# btob.net
KiCad netlist of a schematic drawn in EAGLE
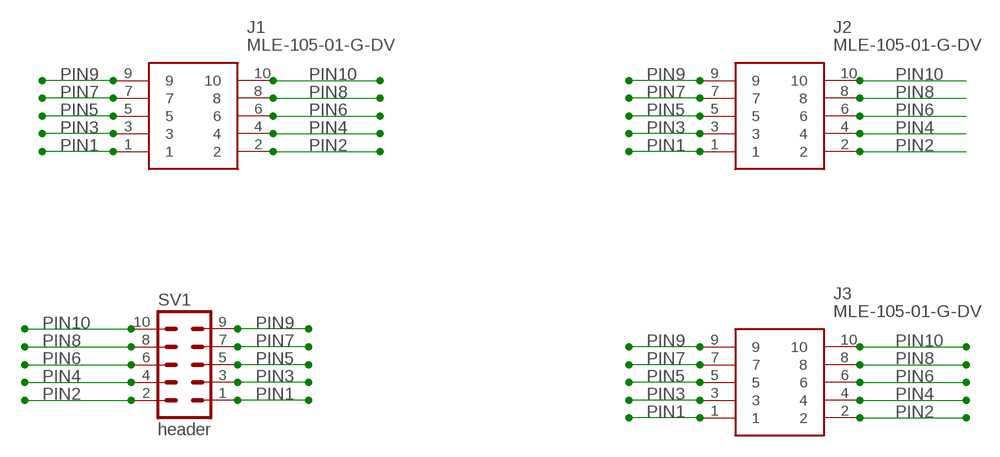
[diagram p0: schematic, sheet 1]

(export (version "E")
  (design (tool "Eeschema 10.0.6"))
  (components
    (comp (ref "J1")
      (value "MLE-105-01-G-DV")
      (footprint "eagle-import:MLE-105-01-G-DV")
      (fields (field (name "MOUSER_PART_NUMBER") "200-MLE10501GDV"))
      (libsource (lib "eagle-import") (part "MLE-105-01-G-DV"))
    )
    (comp (ref "J2")
      (value "MLE-105-01-G-DV")
      (footprint "eagle-import:MLE-105-01-G-DV")
      (fields (field (name "MOUSER_PART_NUMBER") "200-MLE10501GDV"))
      (libsource (lib "eagle-import") (part "MLE-105-01-G-DV"))
    )
    (comp (ref "J3")
      (value "MLE-105-01-G-DV")
      (footprint "eagle-import:MLE-105-01-G-DV")
      (fields (field (name "MOUSER_PART_NUMBER") "200-MLE10501GDV"))
      (libsource (lib "eagle-import") (part "MLE-105-01-G-DV"))
    )
    (comp (ref "SV1")
      (value "header")
      (footprint "eagle-import:MA05-2")
      (libsource (lib "eagle-import") (part "MA05-2"))
    )
  )
  (nets
    (net (code "1") (name "/PIN1") (class "Default")
      (node (ref "J1") (pin "1") (pinfunction "1_1") (pintype "bidirectional"))
      (node (ref "J2") (pin "1") (pinfunction "1_1") (pintype "bidirectional"))
      (node (ref "J3") (pin "1") (pinfunction "1_1") (pintype "bidirectional"))
      (node (ref "SV1") (pin "1") (pinfunction "1_1") (pintype "passive"))
    )
    (net (code "2") (name "/PIN2") (class "Default")
      (node (ref "J1") (pin "2") (pinfunction "2_2") (pintype "bidirectional"))
      (node (ref "J2") (pin "2") (pinfunction "2_2") (pintype "bidirectional"))
      (node (ref "J3") (pin "2") (pinfunction "2_2") (pintype "bidirectional"))
      (node (ref "SV1") (pin "2") (pinfunction "2_2") (pintype "passive"))
    )
    (net (code "3") (name "/PIN3") (class "Default")
      (node (ref "J1") (pin "3") (pinfunction "3_3") (pintype "bidirectional"))
      (node (ref "J2") (pin "3") (pinfunction "3_3") (pintype "bidirectional"))
      (node (ref "J3") (pin "3") (pinfunction "3_3") (pintype "bidirectional"))
      (node (ref "SV1") (pin "3") (pinfunction "3_3") (pintype "passive"))
    )
    (net (code "4") (name "/PIN4") (class "Default")
      (node (ref "J1") (pin "4") (pinfunction "4_4") (pintype "bidirectional"))
      (node (ref "J2") (pin "4") (pinfunction "4_4") (pintype "bidirectional"))
      (node (ref "J3") (pin "4") (pinfunction "4_4") (pintype "bidirectional"))
      (node (ref "SV1") (pin "4") (pinfunction "4_4") (pintype "passive"))
    )
    (net (code "5") (name "/PIN5") (class "Default")
      (node (ref "J1") (pin "5") (pinfunction "5_5") (pintype "bidirectional"))
      (node (ref "J2") (pin "5") (pinfunction "5_5") (pintype "bidirectional"))
      (node (ref "J3") (pin "5") (pinfunction "5_5") (pintype "bidirectional"))
      (node (ref "SV1") (pin "5") (pinfunction "5_5") (pintype "passive"))
    )
    (net (code "6") (name "/PIN6") (class "Default")
      (node (ref "J1") (pin "6") (pinfunction "6_6") (pintype "bidirectional"))
      (node (ref "J2") (pin "6") (pinfunction "6_6") (pintype "bidirectional"))
      (node (ref "J3") (pin "6") (pinfunction "6_6") (pintype "bidirectional"))
      (node (ref "SV1") (pin "6") (pinfunction "6_6") (pintype "passive"))
    )
    (net (code "7") (name "/PIN7") (class "Default")
      (node (ref "J1") (pin "7") (pinfunction "7_7") (pintype "bidirectional"))
      (node (ref "J2") (pin "7") (pinfunction "7_7") (pintype "bidirectional"))
      (node (ref "J3") (pin "7") (pinfunction "7_7") (pintype "bidirectional"))
      (node (ref "SV1") (pin "7") (pinfunction "7_7") (pintype "passive"))
    )
    (net (code "8") (name "/PIN8") (class "Default")
      (node (ref "J1") (pin "8") (pinfunction "8_8") (pintype "bidirectional"))
      (node (ref "J2") (pin "8") (pinfunction "8_8") (pintype "bidirectional"))
      (node (ref "J3") (pin "8") (pinfunction "8_8") (pintype "bidirectional"))
      (node (ref "SV1") (pin "8") (pinfunction "8_8") (pintype "passive"))
    )
    (net (code "9") (name "/PIN9") (class "Default")
      (node (ref "J1") (pin "9") (pinfunction "9_9") (pintype "bidirectional"))
      (node (ref "J2") (pin "9") (pinfunction "9_9") (pintype "bidirectional"))
      (node (ref "J3") (pin "9") (pinfunction "9_9") (pintype "bidirectional"))
      (node (ref "SV1") (pin "9") (pinfunction "9_9") (pintype "passive"))
    )
    (net (code "10") (name "/PIN10") (class "Default")
      (node (ref "J1") (pin "10") (pinfunction "10_10") (pintype "bidirectional"))
      (node (ref "J2") (pin "10") (pinfunction "10_10") (pintype "bidirectional"))
      (node (ref "J3") (pin "10") (pinfunction "10_10") (pintype "bidirectional"))
      (node (ref "SV1") (pin "10") (pinfunction "10_10") (pintype "passive"))
    )
  )
)
